# MB988.net
KiCad netlist of a schematic drawn in Altium Designer
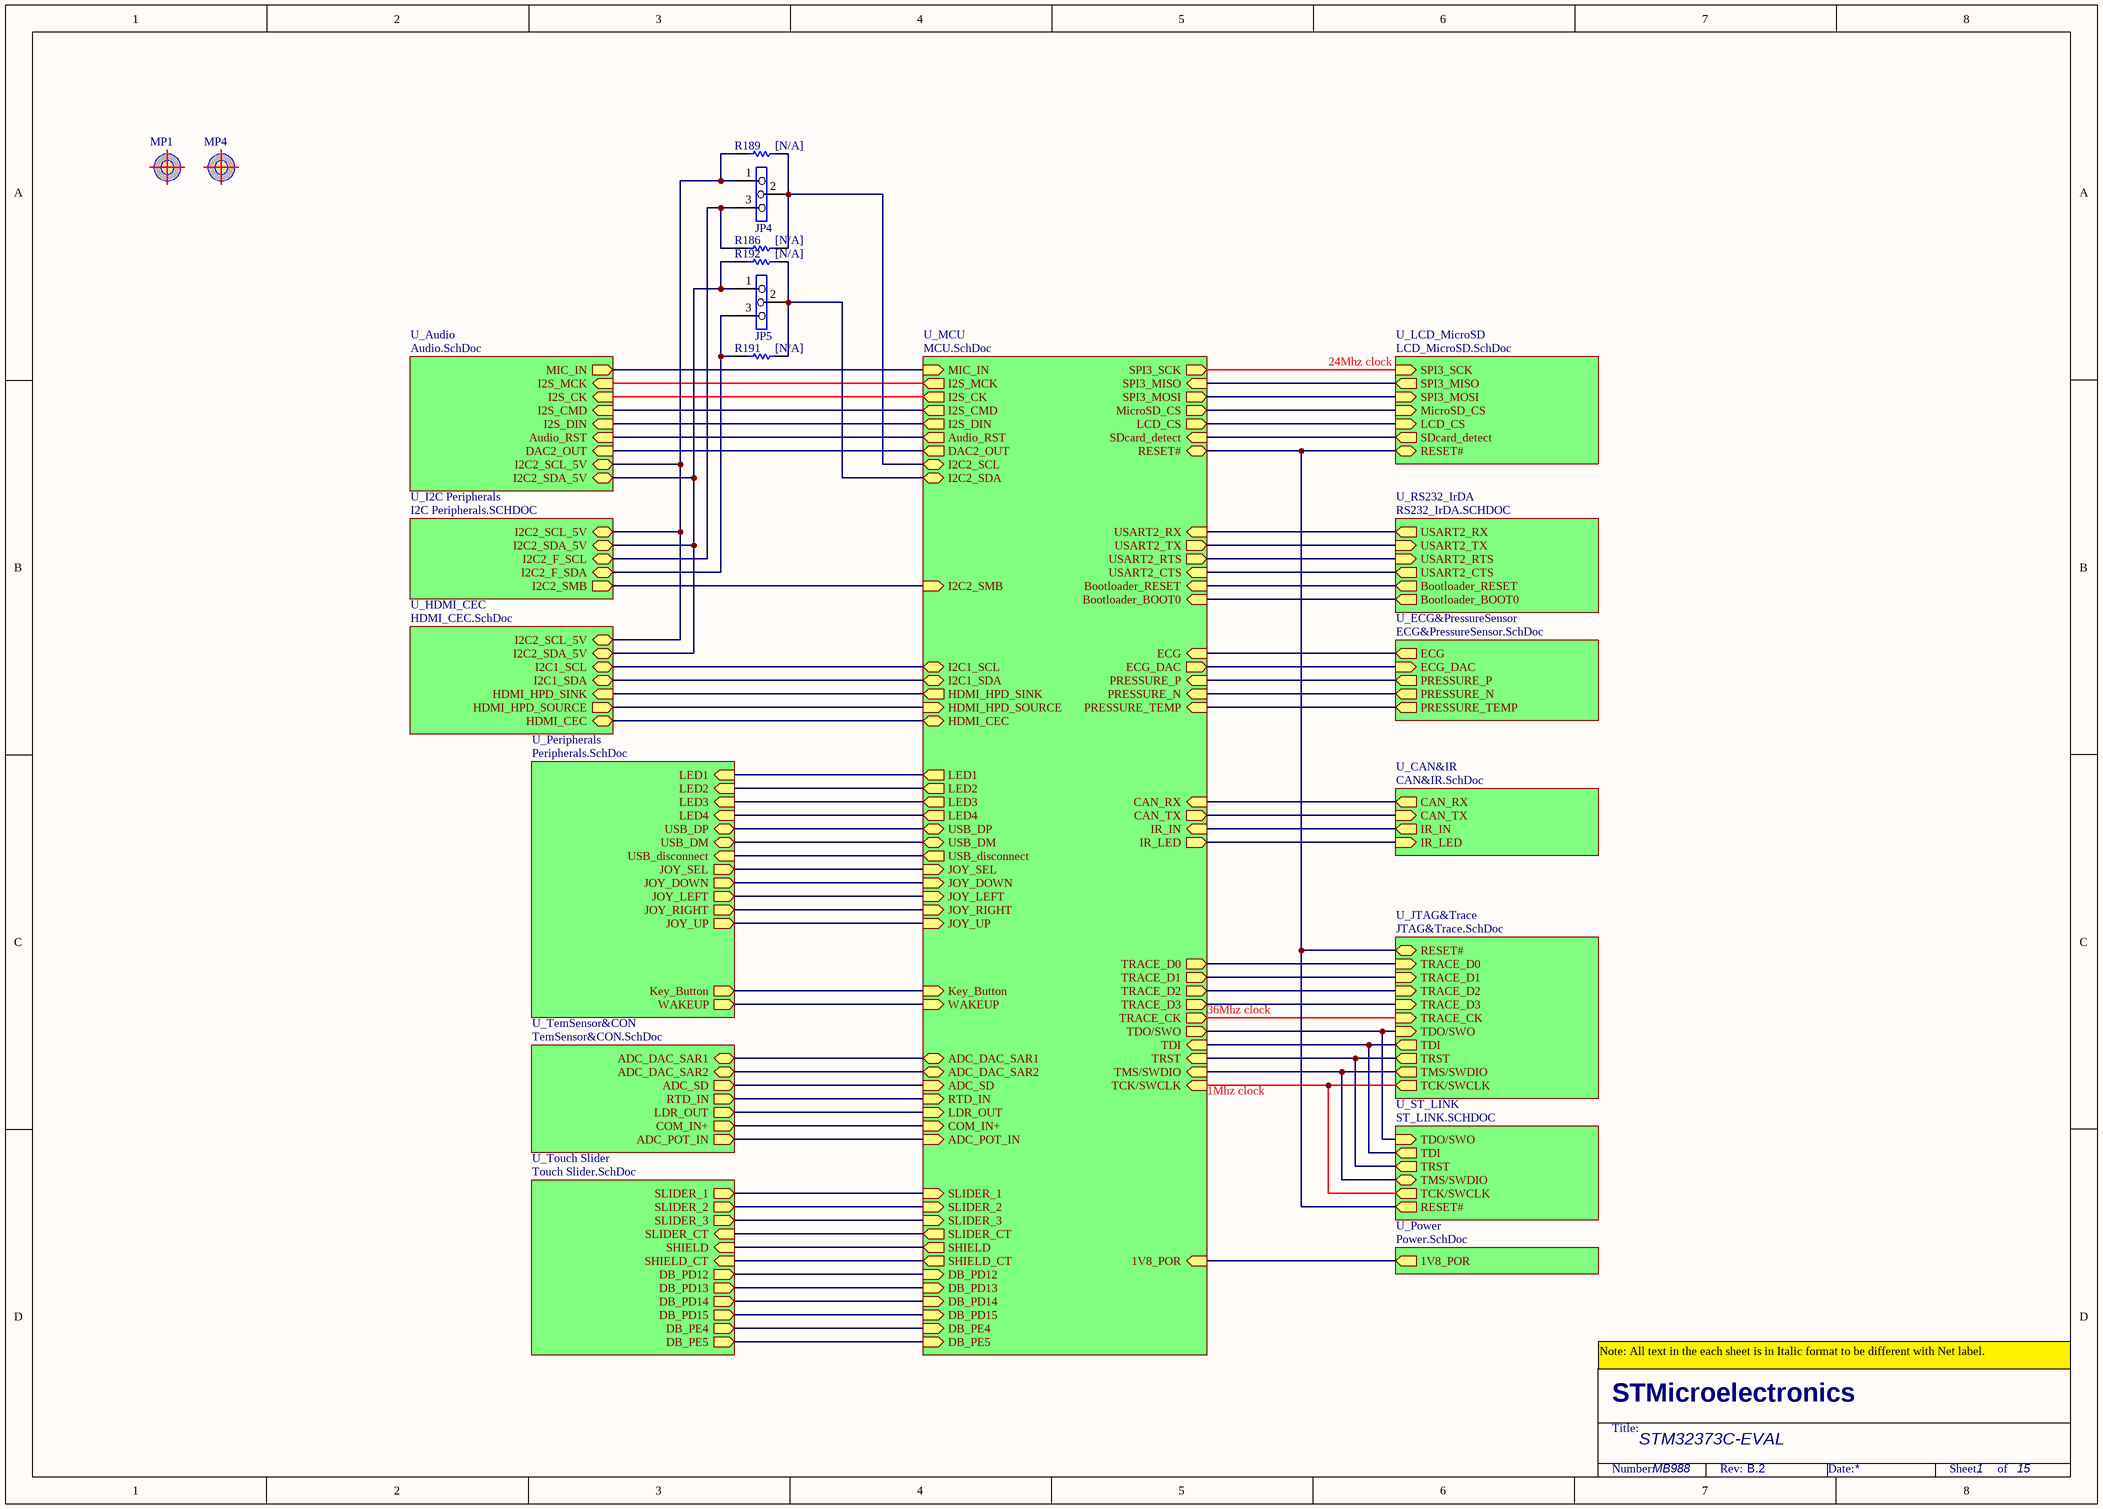
[diagram p0: MB988.SchDoc]

(export (version "E")
  (design (tool "Eeschema 10.0.6"))
  (components
    (comp (ref "JP4") (value "~") (footprint "SIP3") (libsource (lib "STR910_SCHLIB") (part "Jumper3")))
    (comp (ref "JP5") (value "~") (footprint "SIP3") (libsource (lib "STR910_SCHLIB") (part "Jumper3")))
    (comp (ref "MP1") (value "~") (footprint "markpoint_1.0") (libsource (lib "*") (part "MARKPOINT")))
    (comp (ref "MP4") (value "~") (footprint "markpoint_1.0") (libsource (lib "*") (part "MARKPOINT")))
    (comp (ref "R186")
      (value "[N/A]")
      (footprint "0603R")
      (description "Resistor")
      (fields (field (name "PUBLISHER") "Altium Limited"))
      (libsource (lib "Miscellaneous Devices") (part "Res1"))
    )
    (comp (ref "R189")
      (value "[N/A]")
      (footprint "0603R")
      (description "Resistor")
      (fields (field (name "PUBLISHER") "Altium Limited"))
      (libsource (lib "Miscellaneous Devices") (part "Res1"))
    )
    (comp (ref "R191")
      (value "[N/A]")
      (footprint "0603R")
      (description "Resistor")
      (fields (field (name "PUBLISHER") "Altium Limited"))
      (libsource (lib "Miscellaneous Devices") (part "Res1"))
    )
    (comp (ref "R192")
      (value "[N/A]")
      (footprint "0603R")
      (description "Resistor")
      (fields (field (name "PUBLISHER") "Altium Limited"))
      (libsource (lib "Miscellaneous Devices") (part "Res1"))
    )
  )
  (nets
    (net (code "26") (name "/I2C2_F_SCL") (class "Default")
      (node (ref "JP4") (pin "3") (pintype "passive"))
      (node (ref "R186") (pin "2") (pinfunction "2_2") (pintype "passive"))
    )
    (net (code "27") (name "/I2C2_F_SDA") (class "Default")
      (node (ref "JP5") (pin "3") (pintype "passive"))
      (node (ref "R191") (pin "2") (pinfunction "2_2") (pintype "passive"))
    )
    (net (code "28") (name "/I2C2_SCL") (class "Default")
      (node (ref "JP4") (pin "2") (pintype "passive"))
      (node (ref "R186") (pin "1") (pinfunction "1_1") (pintype "passive"))
      (node (ref "R189") (pin "1") (pinfunction "1_1") (pintype "passive"))
    )
    (net (code "29") (name "/I2C2_SCL_5V") (class "Default")
      (node (ref "JP4") (pin "1") (pintype "passive"))
      (node (ref "R189") (pin "2") (pinfunction "2_2") (pintype "passive"))
    )
    (net (code "30") (name "/I2C2_SDA") (class "Default")
      (node (ref "JP5") (pin "2") (pintype "passive"))
      (node (ref "R191") (pin "1") (pinfunction "1_1") (pintype "passive"))
      (node (ref "R192") (pin "1") (pinfunction "1_1") (pintype "passive"))
    )
    (net (code "31") (name "/I2C2_SDA_5V") (class "Default")
      (node (ref "JP5") (pin "1") (pintype "passive"))
      (node (ref "R192") (pin "2") (pinfunction "2_2") (pintype "passive"))
    )
  )
)
